# 3-Axis_Accelerometer.net
KiCad netlist of a schematic drawn in Altium Designer
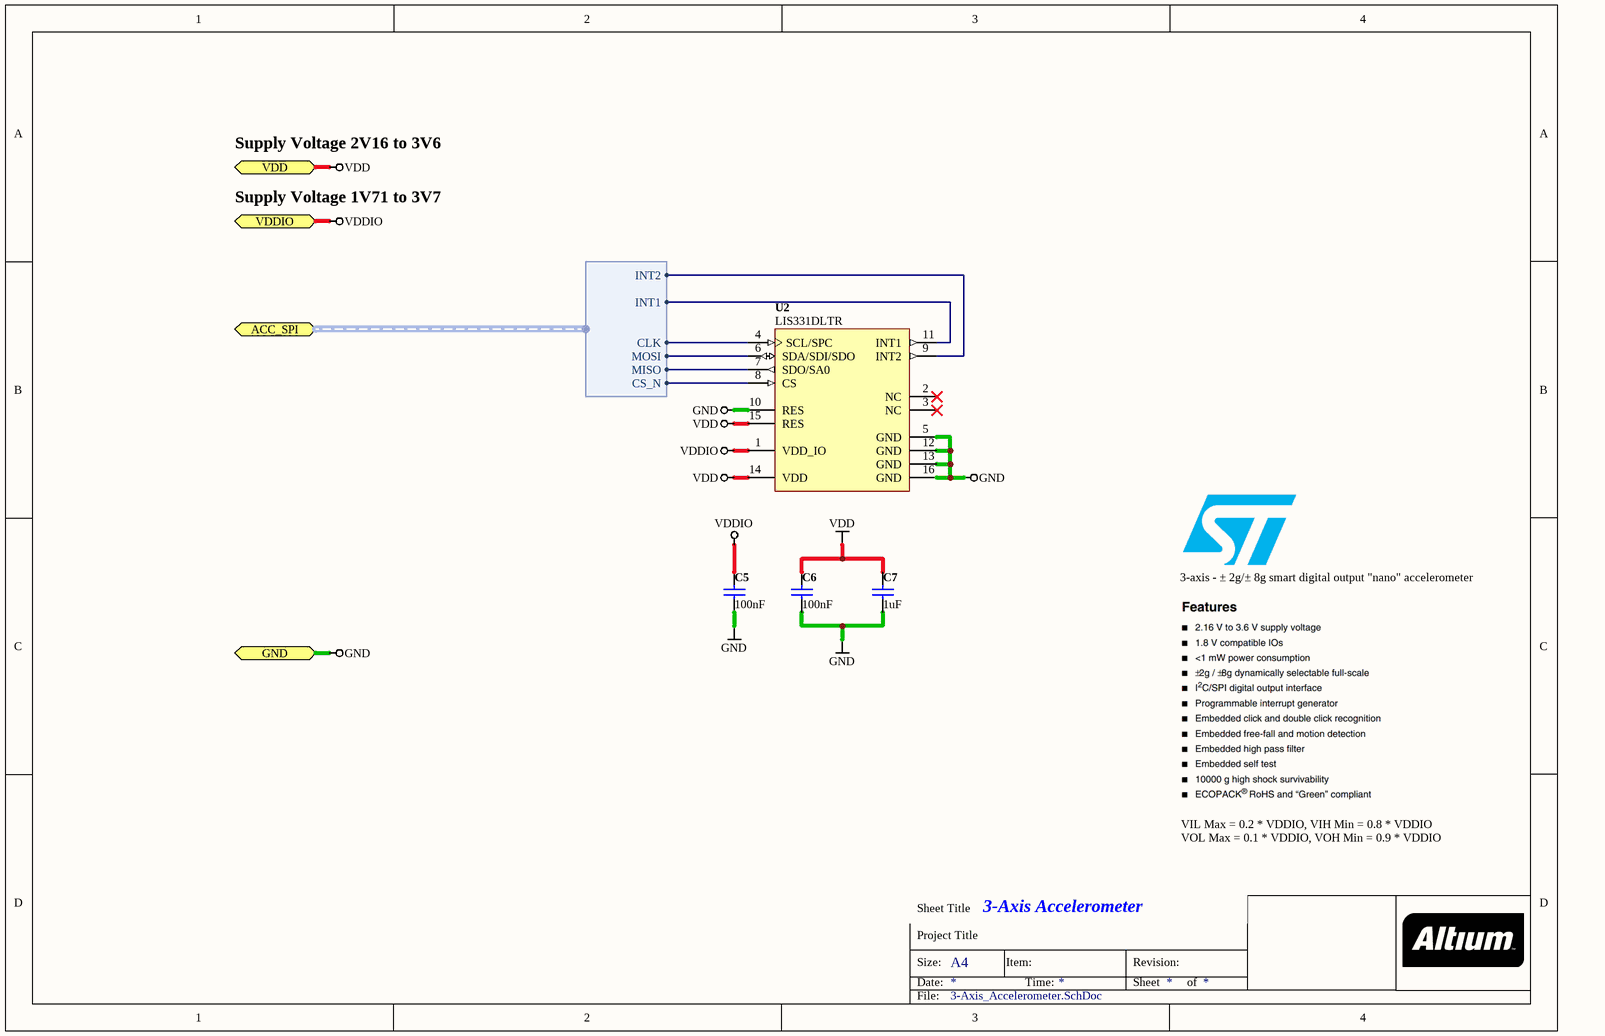
[diagram p0: 3-Axis_Accelerometer.SchDoc]

(export (version "E")
  (design (tool "Eeschema 10.0.6"))
  (components
    (comp (ref "C5")
      (value "100nF")
      (footprint "CAPC0402(1005)60_N")
      (description "CAP 100nF 16V ?0% 0402 (1005 Metric) Thickness 0.6mm SMD")
      (fields (field (name "TOLERANCE") "?0%") (field (name "Comment") "CAP 100nF 16V 0402(1005)"))
      (libsource (lib "Altium Content Vault") (part "CMP-1034-02069-1"))
    )
    (comp (ref "C6")
      (value "100nF")
      (footprint "CAPC0402(1005)60_N")
      (description "CAP 100nF 16V ?0% 0402 (1005 Metric) Thickness 0.6mm SMD")
      (fields (field (name "TOLERANCE") "?0%") (field (name "Comment") "CAP 100nF 16V 0402(1005)"))
      (libsource (lib "Altium Content Vault") (part "CMP-1034-02069-1"))
    )
    (comp (ref "C7")
      (value "1uF")
      (footprint "CAPC0402(1005)60_N")
      (description "CAP 1uF 16V ?0% 0402 (1005 Metric) Thickness 0.6mm SMD")
      (fields (field (name "TOLERANCE") "?0%") (field (name "Comment") "CAP 1uF 16V 0402(1005)"))
      (libsource (lib "Altium Content Vault") (part "CMP-1034-02119-1"))
    )
    (comp (ref "U2")
      (value "LIS331DLTR")
      (footprint "LGA16-3X3X1_L")
      (fields (field (name "MANUFACTURER") "STMicroelectronics"))
      (libsource (lib "Altium Content Vault") (part "CMP-0234-00061-2"))
    )
  )
  (nets
    (net (code "2") (name "/CLK") (class "Default")
      (node (ref "U2") (pin "4") (pinfunction "SCL/SPC_4") (pintype "input"))
    )
    (net (code "3") (name "/CS_N") (class "Default")
      (node (ref "U2") (pin "8") (pinfunction "CS_8") (pintype "input"))
    )
    (net (code "4") (name "/INT1") (class "Default")
      (node (ref "U2") (pin "11") (pinfunction "INT1_11") (pintype "output"))
    )
    (net (code "5") (name "/INT2") (class "Default")
      (node (ref "U2") (pin "9") (pinfunction "INT2_9") (pintype "output"))
    )
    (net (code "6") (name "/MISO") (class "Default")
      (node (ref "U2") (pin "7") (pinfunction "SDO/SA0_7") (pintype "output"))
    )
    (net (code "7") (name "/MOSI") (class "Default")
      (node (ref "U2") (pin "6") (pinfunction "SDA/SDI/SDO_6") (pintype "bidirectional"))
    )
    (net (code "9") (name "GND") (class "Default")
      (node (ref "C5") (pin "2") (pinfunction "2_2") (pintype "passive"))
      (node (ref "C6") (pin "2") (pinfunction "2_2") (pintype "passive"))
      (node (ref "C7") (pin "1") (pinfunction "1_1") (pintype "passive"))
      (node (ref "U2") (pin "10") (pinfunction "RES_10") (pintype "passive"))
      (node (ref "U2") (pin "12") (pinfunction "GND_12") (pintype "power_in"))
      (node (ref "U2") (pin "13") (pinfunction "GND_13") (pintype "power_in"))
      (node (ref "U2") (pin "16") (pinfunction "GND_16") (pintype "power_in"))
      (node (ref "U2") (pin "5") (pinfunction "GND_5") (pintype "power_in"))
    )
    (net (code "10") (name "VDD") (class "Default")
      (node (ref "C6") (pin "1") (pinfunction "1_1") (pintype "passive"))
      (node (ref "C7") (pin "2") (pinfunction "2_2") (pintype "passive"))
      (node (ref "U2") (pin "14") (pinfunction "VDD_14") (pintype "power_in"))
      (node (ref "U2") (pin "15") (pinfunction "RES_15") (pintype "passive"))
    )
    (net (code "11") (name "VDDIO") (class "Default")
      (node (ref "C5") (pin "1") (pinfunction "1_1") (pintype "passive"))
      (node (ref "U2") (pin "1") (pinfunction "VDD_IO_1") (pintype "power_in"))
    )
    (net (code "12") (name "unconnected-(U2-NC-Pad2)") (class "Default")
      (node (ref "U2") (pin "2") (pinfunction "NC_2") (pintype "passive+no_connect"))
    )
    (net (code "13") (name "unconnected-(U2-NC-Pad3)") (class "Default")
      (node (ref "U2") (pin "3") (pinfunction "NC_3") (pintype "passive+no_connect"))
    )
  )
)
